# icetube.net
KiCad netlist of a schematic drawn in EAGLE
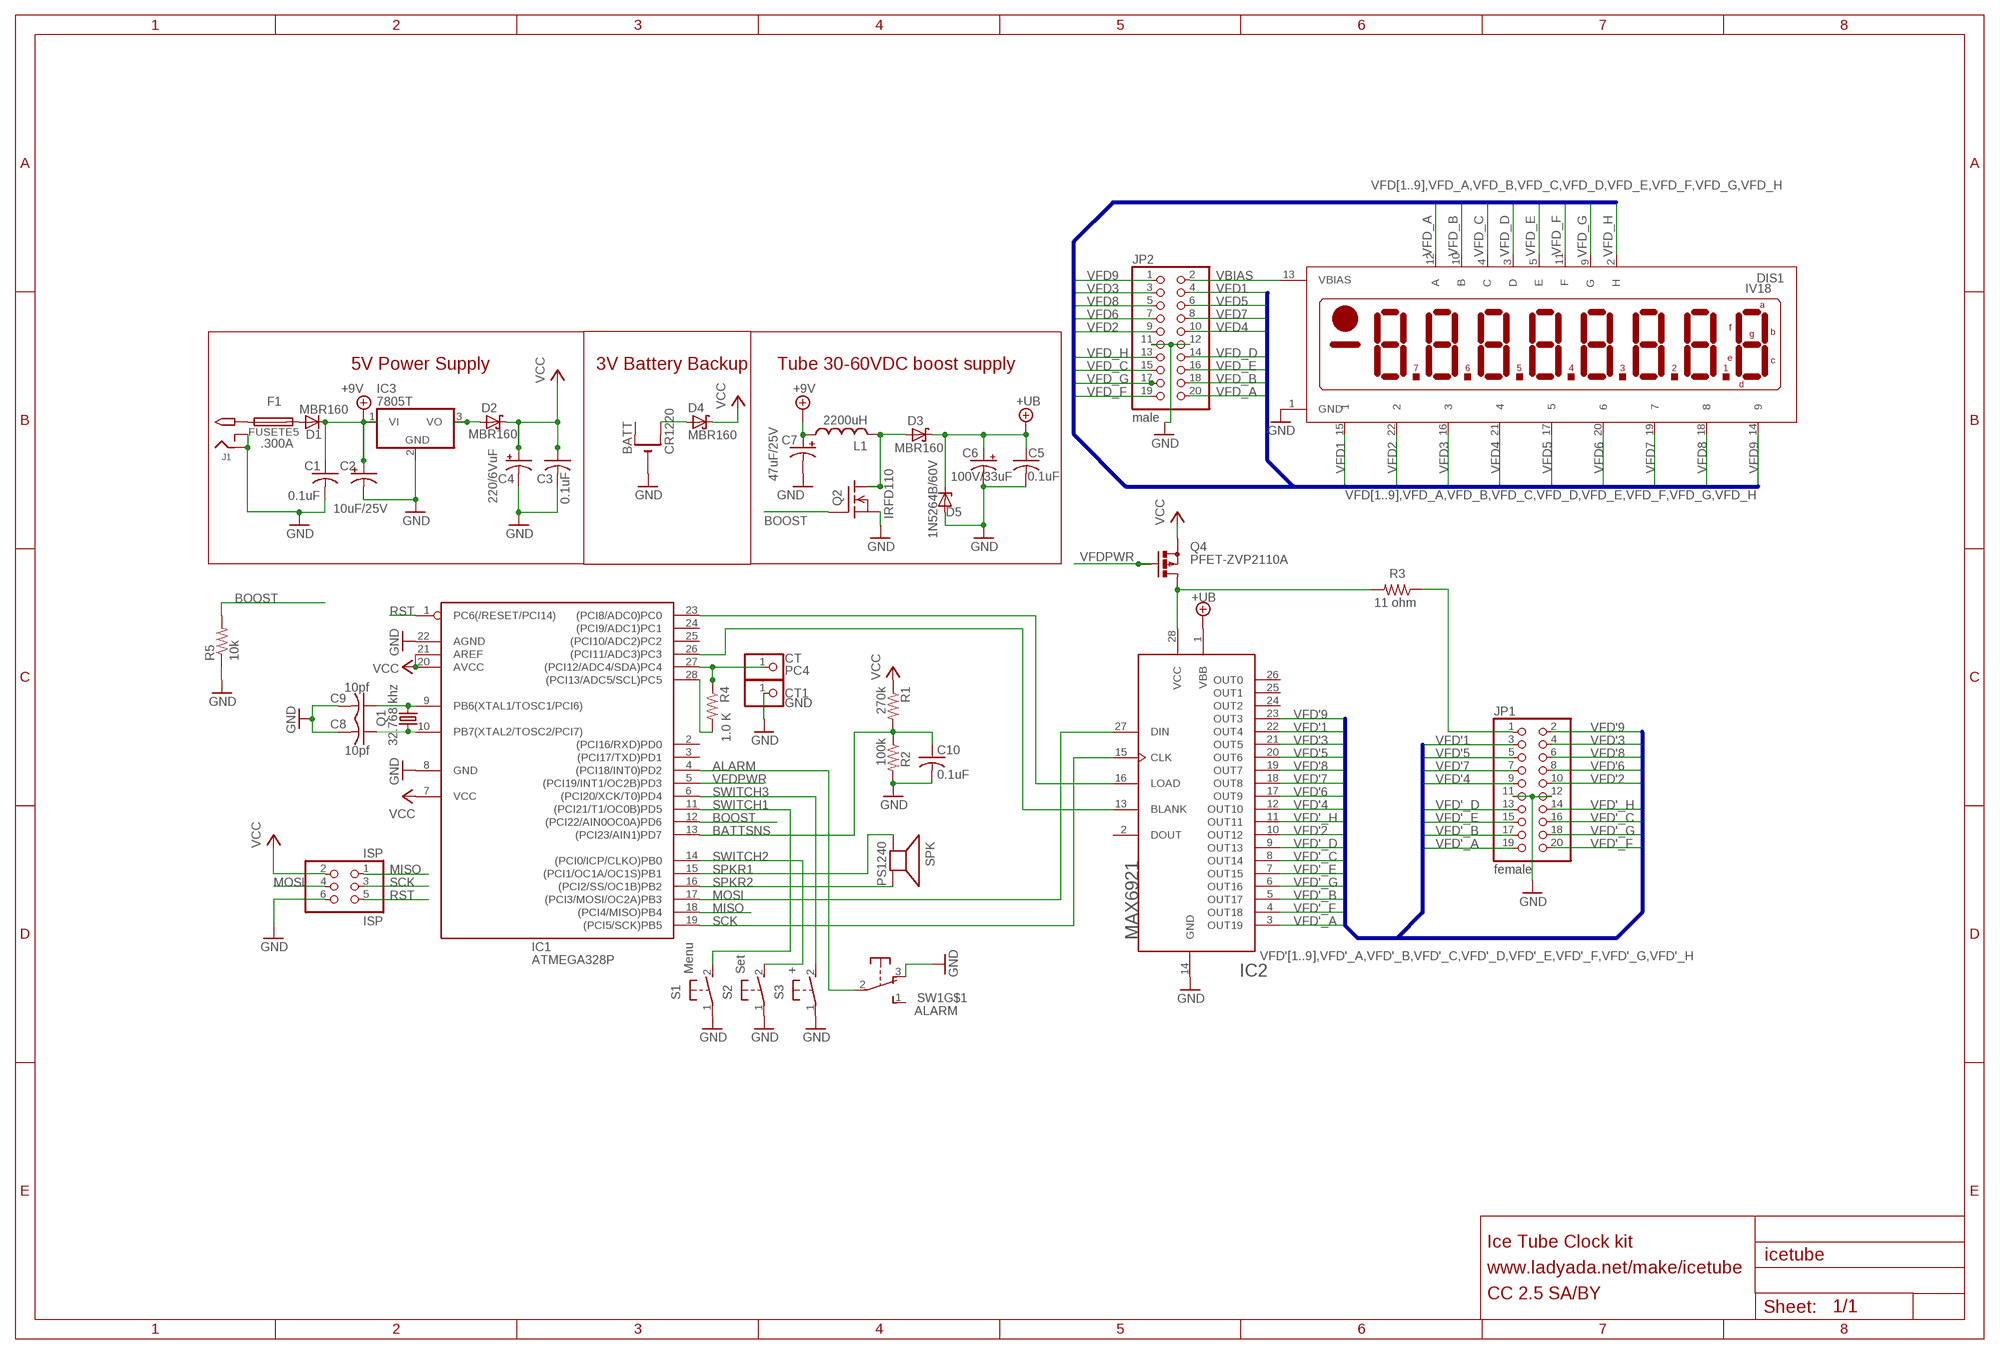
[diagram p0: schematic, sheet 1]

(export (version "E")
  (design (tool "Eeschema 10.0.6"))
  (components
    (comp (ref "BATT")
      (value "CR1220")
      (footprint "eagle-import:CR1220-THM")
      (libsource (lib "eagle-import") (part "CR1220THM"))
    )
    (comp (ref "C1")
      (value "0.1uF")
      (footprint "eagle-import:C025-025X050")
      (libsource (lib "eagle-import") (part "C-US025-025X050"))
    )
    (comp (ref "C2")
      (value "10uF/25V")
      (footprint "eagle-import:E2,5-6")
      (libsource (lib "eagle-import") (part "CPOL-USE2.5-6"))
    )
    (comp (ref "C3")
      (value "0.1uF")
      (footprint "eagle-import:C025-025X050")
      (libsource (lib "eagle-import") (part "C-US025-025X050"))
    )
    (comp (ref "C4")
      (value "220/6VuF")
      (footprint "eagle-import:E2,5-6")
      (libsource (lib "eagle-import") (part "CPOL-USE2.5-6"))
    )
    (comp (ref "C5")
      (value "0.1uF")
      (footprint "eagle-import:C025-024X044")
      (libsource (lib "eagle-import") (part "rcl-ez_C-US025-024X044"))
    )
    (comp (ref "C6")
      (value "100V/33uF")
      (footprint "eagle-import:E3,5-8")
      (libsource (lib "eagle-import") (part "rcl-ez_CPOL-USE3.5-8"))
    )
    (comp (ref "C7")
      (value "47uF/25V")
      (footprint "eagle-import:E2,5-6")
      (libsource (lib "eagle-import") (part "CPOL-USE2.5-6"))
    )
    (comp (ref "C8")
      (value "10pf")
      (footprint "eagle-import:C025-025X050")
      (libsource (lib "eagle-import") (part "C-US025-025X050"))
    )
    (comp (ref "C9")
      (value "10pf")
      (footprint "eagle-import:C025-025X050")
      (libsource (lib "eagle-import") (part "C-US025-025X050"))
    )
    (comp (ref "C10")
      (value "0.1uF")
      (footprint "eagle-import:C025-024X044")
      (libsource (lib "eagle-import") (part "rcl-ez_C-US025-024X044"))
    )
    (comp (ref "CT")
      (value "PC4")
      (footprint "eagle-import:1X01")
      (libsource (lib "eagle-import") (part "PINHD-1X1"))
    )
    (comp (ref "CT1")
      (value "GND")
      (footprint "eagle-import:1X01")
      (libsource (lib "eagle-import") (part "PINHD-1X1"))
    )
    (comp (ref "D1")
      (value "MBR160")
      (footprint "eagle-import:DO41-10")
      (libsource (lib "eagle-import") (part "1N4004"))
    )
    (comp (ref "D2")
      (value "MBR160")
      (footprint "eagle-import:DO41-10")
      (libsource (lib "eagle-import") (part "SCHOTTKY-DIODEDO41"))
    )
    (comp (ref "D3")
      (value "MBR160")
      (footprint "eagle-import:DO41-10")
      (libsource (lib "eagle-import") (part "SCHOTTKY-DIODEDO41"))
    )
    (comp (ref "D4")
      (value "MBR160")
      (footprint "eagle-import:DO41-10")
      (libsource (lib "eagle-import") (part "SCHOTTKY-DIODEDO41"))
    )
    (comp (ref "D5")
      (value "1N5264B/60V")
      (footprint "eagle-import:DO41Z10")
      (libsource (lib "eagle-import") (part "ZENER-DIODEDO41Z10"))
    )
    (comp (ref "DIS1")
      (value "IV18")
      (footprint "eagle-import:IV18")
      (libsource (lib "eagle-import") (part "IV18"))
    )
    (comp (ref "F1")
      (value "FUSETE5")
      (footprint "eagle-import:TE5")
      (fields (field (name "MF") ".300A"))
      (libsource (lib "eagle-import") (part "FUSETE5"))
    )
    (comp (ref "IC1")
      (value "ATMEGA328P")
      (footprint "eagle-import:DIL28_3")
      (libsource (lib "eagle-import") (part "ATMEGA168PROUND"))
    )
    (comp (ref "IC2")
      (value "MAX6921")
      (footprint "eagle-import:PLCC-S28")
      (libsource (lib "eagle-import") (part "MAX6921"))
    )
    (comp (ref "IC3")
      (value "7805T")
      (footprint "eagle-import:TO220H")
      (libsource (lib "eagle-import") (part "78T05"))
    )
    (comp (ref "ISP")
      (value "ISP")
      (footprint "eagle-import:2X03")
      (libsource (lib "eagle-import") (part "PINHD-2X3"))
    )
    (comp (ref "J1")
      (value "2.1MMJACKTHM")
      (footprint "eagle-import:PJ-102A")
      (libsource (lib "eagle-import") (part "2.1MMJACKTHM"))
    )
    (comp (ref "JP1")
      (value "female")
      (footprint "eagle-import:2X10")
      (libsource (lib "eagle-import") (part "PINHD-2X10"))
    )
    (comp (ref "JP2")
      (value "male")
      (footprint "eagle-import:2X10")
      (libsource (lib "eagle-import") (part "PINHD-2X10"))
    )
    (comp (ref "L1")
      (value "2200uH")
      (footprint "eagle-import:6000")
      (libsource (lib "eagle-import") (part "L"))
    )
    (comp (ref "Q1")
      (value "32.768 khz")
      (footprint "eagle-import:TC26V")
      (libsource (lib "eagle-import") (part "CRYTALTC26V"))
    )
    (comp (ref "Q2")
      (value "IRFD110")
      (footprint "eagle-import:DIL04")
      (libsource (lib "eagle-import") (part "IRFD110"))
    )
    (comp (ref "Q4")
      (value "PFET-ZVP2110A")
      (footprint "eagle-import:TO92-OVAL")
      (libsource (lib "eagle-import") (part "PFETZVP3306"))
    )
    (comp (ref "R1")
      (value "270k")
      (footprint "eagle-import:0207_10")
      (libsource (lib "eagle-import") (part "R-US_0207/10"))
    )
    (comp (ref "R2")
      (value "100k")
      (footprint "eagle-import:0207_10")
      (libsource (lib "eagle-import") (part "R-US_0207/10"))
    )
    (comp (ref "R3")
      (value "11 ohm")
      (footprint "eagle-import:0207_10")
      (libsource (lib "eagle-import") (part "R-US_0207/10"))
    )
    (comp (ref "R4")
      (value "1.0 K")
      (footprint "eagle-import:0207_5V")
      (libsource (lib "eagle-import") (part "R-US_0207/5V"))
    )
    (comp (ref "R5")
      (value "10k")
      (footprint "eagle-import:0207_5V")
      (libsource (lib "eagle-import") (part "R-US_0207/5V"))
    )
    (comp (ref "S1")
      (value "Menu")
      (footprint "eagle-import:B3F-31XX")
      (fields (field (name "MPN") "B3F-3100"))
      (libsource (lib "eagle-import") (part "31-XX"))
    )
    (comp (ref "S2")
      (value "Set")
      (footprint "eagle-import:B3F-31XX")
      (fields (field (name "MPN") "B3F-3100"))
      (libsource (lib "eagle-import") (part "31-XX"))
    )
    (comp (ref "S3")
      (value "+")
      (footprint "eagle-import:B3F-31XX")
      (fields (field (name "MPN") "B3F-3100"))
      (libsource (lib "eagle-import") (part "31-XX"))
    )
    (comp (ref "SPK")
      (value "PS1240")
      (footprint "eagle-import:PS12")
      (libsource (lib "eagle-import") (part "SPEAKER/PS12"))
    )
    (comp (ref "SW1")
      (value "ALARM")
      (footprint "eagle-import:OS102011MA1Q")
      (libsource (lib "eagle-import") (part "OS102011MA1Q"))
    )
  )
  (nets
    (net (code "1") (name "+9V") (class "Default")
      (node (ref "C1") (pin "1") (pinfunction "1_1") (pintype "passive"))
      (node (ref "C2") (pin "+") (pinfunction "+_+") (pintype "passive"))
      (node (ref "C7") (pin "+") (pinfunction "+_+") (pintype "passive"))
      (node (ref "D1") (pin "C") (pinfunction "C_C") (pintype "passive"))
      (node (ref "IC3") (pin "1") (pinfunction "VI_1") (pintype "input"))
      (node (ref "L1") (pin "1") (pinfunction "1_1") (pintype "passive"))
    )
    (net (code "2") (name "+UB") (class "Default")
      (node (ref "C5") (pin "1") (pinfunction "1_1") (pintype "passive"))
      (node (ref "C6") (pin "+") (pinfunction "+_+") (pintype "passive"))
      (node (ref "D3") (pin "C") (pinfunction "C_C") (pintype "passive"))
      (node (ref "D5") (pin "C") (pinfunction "C_C") (pintype "passive"))
      (node (ref "IC2") (pin "1") (pinfunction "VBB_1") (pintype "power_in"))
    )
    (net (code "3") (name "/ALARM") (class "Default")
      (node (ref "IC1") (pin "4") (pinfunction "(PCI18/INT0)PD2_4") (pintype "bidirectional"))
      (node (ref "SW1") (pin "2") (pinfunction "P_2") (pintype "passive"))
    )
    (net (code "4") (name "/BATTSNS") (class "Default")
      (node (ref "C10") (pin "1") (pinfunction "1_1") (pintype "passive"))
      (node (ref "IC1") (pin "13") (pinfunction "(PCI23/AIN1)PD7_13") (pintype "bidirectional"))
      (node (ref "R1") (pin "2") (pinfunction "2_2") (pintype "passive"))
      (node (ref "R2") (pin "1") (pinfunction "1_1") (pintype "passive"))
    )
    (net (code "5") (name "/BOOST") (class "Default")
      (node (ref "IC1") (pin "12") (pinfunction "(PCI22/AIN0OC0A)PD6_12") (pintype "bidirectional"))
      (node (ref "Q2") (pin "3") (pinfunction "G_3") (pintype "passive"))
      (node (ref "R5") (pin "2") (pinfunction "2_2") (pintype "passive"))
    )
    (net (code "6") (name "/MISO") (class "Default")
      (node (ref "IC1") (pin "18") (pinfunction "(PCI4/MISO)PB4_18") (pintype "bidirectional"))
      (node (ref "ISP") (pin "1") (pinfunction "1_1") (pintype "passive"))
    )
    (net (code "7") (name "/MOSI") (class "Default")
      (node (ref "IC1") (pin "17") (pinfunction "(PCI3/MOSI/OC2A)PB3_17") (pintype "bidirectional"))
      (node (ref "IC2") (pin "27") (pinfunction "DIN_27") (pintype "input"))
      (node (ref "ISP") (pin "4") (pinfunction "4_4") (pintype "passive"))
    )
    (net (code "8") (name "/RST") (class "Default")
      (node (ref "IC1") (pin "1") (pinfunction "PC6(/RESET/PCI14)_1") (pintype "bidirectional"))
      (node (ref "ISP") (pin "5") (pinfunction "5_5") (pintype "passive"))
    )
    (net (code "9") (name "/SCK") (class "Default")
      (node (ref "IC1") (pin "19") (pinfunction "(PCI5/SCK)PB5_19") (pintype "bidirectional"))
      (node (ref "IC2") (pin "15") (pinfunction "CLK_15") (pintype "input"))
      (node (ref "ISP") (pin "3") (pinfunction "3_3") (pintype "passive"))
    )
    (net (code "10") (name "/SPKR1") (class "Default")
      (node (ref "IC1") (pin "15") (pinfunction "(PCI1/OC1A/OC1S)PB1_15") (pintype "bidirectional"))
      (node (ref "SPK") (pin "P$1") (pinfunction "+_P$1") (pintype "passive"))
    )
    (net (code "11") (name "/SPKR2") (class "Default")
      (node (ref "IC1") (pin "16") (pinfunction "(PCI2/SS/OC1B)PB2_16") (pintype "bidirectional"))
      (node (ref "SPK") (pin "P$2") (pinfunction "-_P$2") (pintype "passive"))
    )
    (net (code "12") (name "/SWITCH1") (class "Default")
      (node (ref "IC1") (pin "11") (pinfunction "(PCI21/T1/OC0B)PD5_11") (pintype "bidirectional"))
      (node (ref "S1") (pin "2") (pinfunction "S_2") (pintype "passive"))
    )
    (net (code "13") (name "/SWITCH2") (class "Default")
      (node (ref "IC1") (pin "14") (pinfunction "(PCI0/ICP/CLKO)PB0_14") (pintype "bidirectional"))
      (node (ref "S2") (pin "2") (pinfunction "S_2") (pintype "passive"))
    )
    (net (code "14") (name "/SWITCH3") (class "Default")
      (node (ref "IC1") (pin "6") (pinfunction "(PCI20/XCK/T0)PD4_6") (pintype "bidirectional"))
      (node (ref "S3") (pin "2") (pinfunction "S_2") (pintype "passive"))
    )
    (net (code "15") (name "/VBIAS") (class "Default")
      (node (ref "DIS1") (pin "13") (pinfunction "VBIAS_13") (pintype "power_in"))
      (node (ref "JP2") (pin "2") (pinfunction "2_2") (pintype "passive"))
    )
    (net (code "16") (name "/VFD'1") (class "Default")
      (node (ref "IC2") (pin "22") (pinfunction "OUT4_22") (pintype "output"))
      (node (ref "JP1") (pin "3") (pinfunction "3_3") (pintype "passive"))
    )
    (net (code "17") (name "/VFD'2") (class "Default")
      (node (ref "IC2") (pin "10") (pinfunction "OUT12_10") (pintype "output"))
      (node (ref "JP1") (pin "10") (pinfunction "10_10") (pintype "passive"))
    )
    (net (code "18") (name "/VFD'3") (class "Default")
      (node (ref "IC2") (pin "21") (pinfunction "OUT5_21") (pintype "output"))
      (node (ref "JP1") (pin "4") (pinfunction "4_4") (pintype "passive"))
    )
    (net (code "19") (name "/VFD'4") (class "Default")
      (node (ref "IC2") (pin "12") (pinfunction "OUT10_12") (pintype "output"))
      (node (ref "JP1") (pin "9") (pinfunction "9_9") (pintype "passive"))
    )
    (net (code "20") (name "/VFD'5") (class "Default")
      (node (ref "IC2") (pin "20") (pinfunction "OUT6_20") (pintype "output"))
      (node (ref "JP1") (pin "5") (pinfunction "5_5") (pintype "passive"))
    )
    (net (code "21") (name "/VFD'6") (class "Default")
      (node (ref "IC2") (pin "17") (pinfunction "OUT9_17") (pintype "output"))
      (node (ref "JP1") (pin "8") (pinfunction "8_8") (pintype "passive"))
    )
    (net (code "22") (name "/VFD'7") (class "Default")
      (node (ref "IC2") (pin "18") (pinfunction "OUT8_18") (pintype "output"))
      (node (ref "JP1") (pin "7") (pinfunction "7_7") (pintype "passive"))
    )
    (net (code "23") (name "/VFD'8") (class "Default")
      (node (ref "IC2") (pin "19") (pinfunction "OUT7_19") (pintype "output"))
      (node (ref "JP1") (pin "6") (pinfunction "6_6") (pintype "passive"))
    )
    (net (code "24") (name "/VFD'9") (class "Default")
      (node (ref "IC2") (pin "23") (pinfunction "OUT3_23") (pintype "output"))
      (node (ref "JP1") (pin "2") (pinfunction "2_2") (pintype "passive"))
    )
    (net (code "25") (name "/VFD'_A") (class "Default")
      (node (ref "IC2") (pin "3") (pinfunction "OUT19_3") (pintype "output"))
      (node (ref "JP1") (pin "19") (pinfunction "19_19") (pintype "passive"))
    )
    (net (code "26") (name "/VFD'_B") (class "Default")
      (node (ref "IC2") (pin "5") (pinfunction "OUT17_5") (pintype "output"))
      (node (ref "JP1") (pin "17") (pinfunction "17_17") (pintype "passive"))
    )
    (net (code "27") (name "/VFD'_C") (class "Default")
      (node (ref "IC2") (pin "8") (pinfunction "OUT14_8") (pintype "output"))
      (node (ref "JP1") (pin "16") (pinfunction "16_16") (pintype "passive"))
    )
    (net (code "28") (name "/VFD'_D") (class "Default")
      (node (ref "IC2") (pin "9") (pinfunction "OUT13_9") (pintype "output"))
      (node (ref "JP1") (pin "13") (pinfunction "13_13") (pintype "passive"))
    )
    (net (code "29") (name "/VFD'_E") (class "Default")
      (node (ref "IC2") (pin "7") (pinfunction "OUT15_7") (pintype "output"))
      (node (ref "JP1") (pin "15") (pinfunction "15_15") (pintype "passive"))
    )
    (net (code "30") (name "/VFD'_F") (class "Default")
      (node (ref "IC2") (pin "4") (pinfunction "OUT18_4") (pintype "output"))
      (node (ref "JP1") (pin "20") (pinfunction "20_20") (pintype "passive"))
    )
    (net (code "31") (name "/VFD'_G") (class "Default")
      (node (ref "IC2") (pin "6") (pinfunction "OUT16_6") (pintype "output"))
      (node (ref "JP1") (pin "18") (pinfunction "18_18") (pintype "passive"))
    )
    (net (code "32") (name "/VFD'_H") (class "Default")
      (node (ref "IC2") (pin "11") (pinfunction "OUT11_11") (pintype "output"))
      (node (ref "JP1") (pin "14") (pinfunction "14_14") (pintype "passive"))
    )
    (net (code "33") (name "/VFD1") (class "Default")
      (node (ref "DIS1") (pin "15") (pinfunction "1_15") (pintype "passive"))
      (node (ref "JP2") (pin "4") (pinfunction "4_4") (pintype "passive"))
    )
    (net (code "34") (name "/VFD2") (class "Default")
      (node (ref "DIS1") (pin "22") (pinfunction "2_22") (pintype "passive"))
      (node (ref "JP2") (pin "9") (pinfunction "9_9") (pintype "passive"))
    )
    (net (code "35") (name "/VFD3") (class "Default")
      (node (ref "DIS1") (pin "16") (pinfunction "3_16") (pintype "passive"))
      (node (ref "JP2") (pin "3") (pinfunction "3_3") (pintype "passive"))
    )
    (net (code "36") (name "/VFD4") (class "Default")
      (node (ref "DIS1") (pin "21") (pinfunction "4_21") (pintype "passive"))
      (node (ref "JP2") (pin "10") (pinfunction "10_10") (pintype "passive"))
    )
    (net (code "37") (name "/VFD5") (class "Default")
      (node (ref "DIS1") (pin "17") (pinfunction "5_17") (pintype "passive"))
      (node (ref "JP2") (pin "6") (pinfunction "6_6") (pintype "passive"))
    )
    (net (code "38") (name "/VFD6") (class "Default")
      (node (ref "DIS1") (pin "20") (pinfunction "6_20") (pintype "passive"))
      (node (ref "JP2") (pin "7") (pinfunction "7_7") (pintype "passive"))
    )
    (net (code "39") (name "/VFD7") (class "Default")
      (node (ref "DIS1") (pin "19") (pinfunction "7_19") (pintype "passive"))
      (node (ref "JP2") (pin "8") (pinfunction "8_8") (pintype "passive"))
    )
    (net (code "40") (name "/VFD8") (class "Default")
      (node (ref "DIS1") (pin "18") (pinfunction "8_18") (pintype "passive"))
      (node (ref "JP2") (pin "5") (pinfunction "5_5") (pintype "passive"))
    )
    (net (code "41") (name "/VFD9") (class "Default")
      (node (ref "DIS1") (pin "14") (pinfunction "9_14") (pintype "passive"))
      (node (ref "JP2") (pin "1") (pinfunction "1_1") (pintype "passive"))
    )
    (net (code "42") (name "/VFDPWR") (class "Default")
      (node (ref "IC1") (pin "5") (pinfunction "(PCI19/INT1/OC2B)PD3_5") (pintype "bidirectional"))
      (node (ref "Q4") (pin "2") (pinfunction "G_2") (pintype "passive"))
    )
    (net (code "43") (name "/VFD_A") (class "Default")
      (node (ref "DIS1") (pin "12") (pinfunction "A_12") (pintype "passive"))
      (node (ref "JP2") (pin "20") (pinfunction "20_20") (pintype "passive"))
    )
    (net (code "44") (name "/VFD_B") (class "Default")
      (node (ref "DIS1") (pin "10") (pinfunction "B_10") (pintype "passive"))
      (node (ref "JP2") (pin "18") (pinfunction "18_18") (pintype "passive"))
    )
    (net (code "45") (name "/VFD_C") (class "Default")
      (node (ref "DIS1") (pin "4") (pinfunction "C_4") (pintype "passive"))
      (node (ref "JP2") (pin "15") (pinfunction "15_15") (pintype "passive"))
    )
    (net (code "46") (name "/VFD_D") (class "Default")
      (node (ref "DIS1") (pin "3") (pinfunction "D_3") (pintype "passive"))
      (node (ref "JP2") (pin "14") (pinfunction "14_14") (pintype "passive"))
    )
    (net (code "47") (name "/VFD_E") (class "Default")
      (node (ref "DIS1") (pin "5") (pinfunction "E_5") (pintype "passive"))
      (node (ref "JP2") (pin "16") (pinfunction "16_16") (pintype "passive"))
    )
    (net (code "48") (name "/VFD_F") (class "Default")
      (node (ref "DIS1") (pin "11") (pinfunction "F_11") (pintype "passive"))
      (node (ref "JP2") (pin "19") (pinfunction "19_19") (pintype "passive"))
    )
    (net (code "49") (name "/VFD_G") (class "Default")
      (node (ref "DIS1") (pin "9") (pinfunction "G_9") (pintype "passive"))
      (node (ref "JP2") (pin "17") (pinfunction "17_17") (pintype "passive"))
    )
    (net (code "50") (name "/VFD_H") (class "Default")
      (node (ref "DIS1") (pin "2") (pinfunction "H_2") (pintype "passive"))
      (node (ref "JP2") (pin "13") (pinfunction "13_13") (pintype "passive"))
    )
    (net (code "53") (name "GND") (class "Default")
      (node (ref "BATT") (pin "-") (pinfunction "-_-") (pintype "passive"))
      (node (ref "C1") (pin "2") (pinfunction "2_2") (pintype "passive"))
      (node (ref "C10") (pin "2") (pinfunction "2_2") (pintype "passive"))
      (node (ref "C2") (pin "-") (pinfunction "-_-") (pintype "passive"))
      (node (ref "C3") (pin "2") (pinfunction "2_2") (pintype "passive"))
      (node (ref "C4") (pin "-") (pinfunction "-_-") (pintype "passive"))
      (node (ref "C5") (pin "2") (pinfunction "2_2") (pintype "passive"))
      (node (ref "C6") (pin "-") (pinfunction "-_-") (pintype "passive"))
      (node (ref "C7") (pin "-") (pinfunction "-_-") (pintype "passive"))
      (node (ref "C8") (pin "2") (pinfunction "2_2") (pintype "passive"))
      (node (ref "C9") (pin "2") (pinfunction "2_2") (pintype "passive"))
      (node (ref "CT1") (pin "1") (pinfunction "1_1") (pintype "passive"))
      (node (ref "D5") (pin "A") (pinfunction "A_A") (pintype "passive"))
      (node (ref "DIS1") (pin "1") (pinfunction "GND_1") (pintype "power_in"))
      (node (ref "IC1") (pin "22") (pinfunction "AGND_22") (pintype "bidirectional"))
      (node (ref "IC1") (pin "8") (pinfunction "GND_8") (pintype "bidirectional"))
      (node (ref "IC2") (pin "14") (pinfunction "GND_14") (pintype "power_in"))
      (node (ref "IC3") (pin "2") (pinfunction "GND_2") (pintype "passive"))
      (node (ref "ISP") (pin "6") (pinfunction "6_6") (pintype "passive"))
      (node (ref "J1") (pin "RING") (pinfunction "RING_RING") (pintype "bidirectional"))
      (node (ref "J1") (pin "RING_SW") (pinfunction "RING_SW_RING_SW") (pintype "bidirectional"))
      (node (ref "JP1") (pin "11") (pinfunction "11_11") (pintype "passive"))
      (node (ref "JP1") (pin "12") (pinfunction "12_12") (pintype "passive"))
      (node (ref "JP2") (pin "11") (pinfunction "11_11") (pintype "passive"))
      (node (ref "JP2") (pin "12") (pinfunction "12_12") (pintype "passive"))
      (node (ref "Q2") (pin "4") (pinfunction "S_4") (pintype "passive"))
      (node (ref "R2") (pin "2") (pinfunction "2_2") (pintype "passive"))
      (node (ref "R5") (pin "1") (pinfunction "1_1") (pintype "passive"))
      (node (ref "S1") (pin "1") (pinfunction "P_1") (pintype "passive"))
      (node (ref "S2") (pin "1") (pinfunction "P_1") (pintype "passive"))
      (node (ref "S3") (pin "1") (pinfunction "P_1") (pintype "passive"))
      (node (ref "SW1") (pin "3") (pinfunction "O_3") (pintype "passive"))
    )
    (net (code "54") (name "Net-(BATT-+1)") (class "Default")
      (node (ref "BATT") (pin "+2") (pinfunction "+1_+2") (pintype "passive"))
      (node (ref "D4") (pin "A") (pinfunction "A_A") (pintype "passive"))
    )
    (net (code "55") (name "Net-(D1-PadA)") (class "Default")
      (node (ref "D1") (pin "A") (pinfunction "A_A") (pintype "passive"))
      (node (ref "F1") (pin "2") (pinfunction "2_2") (pintype "passive"))
    )
    (net (code "56") (name "Net-(F1-Pad1)") (class "Default")
      (node (ref "F1") (pin "1") (pinfunction "1_1") (pintype "passive"))
      (node (ref "J1") (pin "TIP") (pinfunction "TIP_TIP") (pintype "bidirectional"))
    )
    (net (code "57") (name "Net-(IC1-(PCI8{slash}ADC0)PC0)") (class "Default")
      (node (ref "IC1") (pin "23") (pinfunction "(PCI8/ADC0)PC0_23") (pintype "bidirectional"))
      (node (ref "IC2") (pin "16") (pinfunction "LOAD_16") (pintype "input"))
    )
    (net (code "58") (name "Net-(IC1-(PCI11{slash}ADC3)PC3)") (class "Default")
      (node (ref "IC1") (pin "26") (pinfunction "(PCI11/ADC3)PC3_26") (pintype "bidirectional"))
      (node (ref "IC2") (pin "13") (pinfunction "BLANK_13") (pintype "input"))
    )
    (net (code "59") (name "Net-(IC1-(PCI12{slash}ADC4{slash}SDA)PC4)") (class "Default")
      (node (ref "CT") (pin "1") (pinfunction "1_1") (pintype "passive"))
      (node (ref "IC1") (pin "27") (pinfunction "(PCI12/ADC4/SDA)PC4_27") (pintype "bidirectional"))
      (node (ref "R4") (pin "1") (pinfunction "1_1") (pintype "passive"))
    )
    (net (code "60") (name "Net-(IC1-(PCI13{slash}ADC5{slash}SCL)PC5)") (class "Default")
      (node (ref "IC1") (pin "28") (pinfunction "(PCI13/ADC5/SCL)PC5_28") (pintype "bidirectional"))
      (node (ref "R4") (pin "2") (pinfunction "2_2") (pintype "passive"))
    )
    (net (code "61") (name "Net-(IC1-PB6(XTAL1{slash}TOSC1{slash}PCI6))") (class "Default")
      (node (ref "C9") (pin "1") (pinfunction "1_1") (pintype "passive"))
      (node (ref "IC1") (pin "9") (pinfunction "PB6(XTAL1/TOSC1/PCI6)_9") (pintype "bidirectional"))
      (node (ref "Q1") (pin "2") (pinfunction "2_2") (pintype "passive"))
    )
    (net (code "62") (name "Net-(IC1-PB7(XTAL2{slash}TOSC2{slash}PCI7))") (class "Default")
      (node (ref "C8") (pin "1") (pinfunction "1_1") (pintype "passive"))
      (node (ref "IC1") (pin "10") (pinfunction "PB7(XTAL2/TOSC2/PCI7)_10") (pintype "bidirectional"))
      (node (ref "Q1") (pin "1") (pinfunction "1_1") (pintype "passive"))
    )
    (net (code "63") (name "Net-(IC2-VCC)") (class "Default")
      (node (ref "IC2") (pin "28") (pinfunction "VCC_28") (pintype "power_in"))
      (node (ref "Q4") (pin "3") (pinfunction "D_3") (pintype "passive"))
      (node (ref "R3") (pin "2") (pinfunction "2_2") (pintype "passive"))
    )
    (net (code "64") (name "Net-(IC3-VO)") (class "Default")
      (node (ref "D2") (pin "A") (pinfunction "A_A") (pintype "passive"))
      (node (ref "IC3") (pin "3") (pinfunction "VO_3") (pintype "passive"))
    )
    (net (code "65") (name "Net-(JP1-Pad1)") (class "Default")
      (node (ref "JP1") (pin "1") (pinfunction "1_1") (pintype "passive"))
      (node (ref "R3") (pin "1") (pinfunction "1_1") (pintype "passive"))
    )
    (net (code "66") (name "Net-(Q2-D)") (class "Default")
      (node (ref "D3") (pin "A") (pinfunction "A_A") (pintype "passive"))
      (node (ref "L1") (pin "2") (pinfunction "2_2") (pintype "passive"))
      (node (ref "Q2") (pin "1") (pinfunction "D_1") (pintype "passive"))
      (node (ref "Q2") (pin "2") (pinfunction "D1_2") (pintype "passive"))
    )
    (net (code "67") (name "VCC") (class "Default")
      (node (ref "C3") (pin "1") (pinfunction "1_1") (pintype "passive"))
      (node (ref "C4") (pin "+") (pinfunction "+_+") (pintype "passive"))
      (node (ref "D2") (pin "C") (pinfunction "C_C") (pintype "passive"))
      (node (ref "D4") (pin "C") (pinfunction "C_C") (pintype "passive"))
      (node (ref "IC1") (pin "20") (pinfunction "AVCC_20") (pintype "bidirectional"))
      (node (ref "IC1") (pin "21") (pinfunction "AREF_21") (pintype "bidirectional"))
      (node (ref "IC1") (pin "7") (pinfunction "VCC_7") (pintype "bidirectional"))
      (node (ref "ISP") (pin "2") (pinfunction "2_2") (pintype "passive"))
      (node (ref "Q4") (pin "1") (pinfunction "S_1") (pintype "passive"))
      (node (ref "R1") (pin "1") (pinfunction "1_1") (pintype "passive"))
    )
    (net (code "68") (name "unconnected-(BATT-+-Pad+1)") (class "Default")
      (node (ref "BATT") (pin "+1") (pinfunction "+_+1") (pintype "passive"))
    )
    (net (code "69") (name "unconnected-(IC1-(PCI9{slash}ADC1)PC1-Pad24)") (class "Default")
      (node (ref "IC1") (pin "24") (pinfunction "(PCI9/ADC1)PC1_24") (pintype "bidirectional"))
    )
    (net (code "70") (name "unconnected-(IC1-(PCI10{slash}ADC2)PC2-Pad25)") (class "Default")
      (node (ref "IC1") (pin "25") (pinfunction "(PCI10/ADC2)PC2_25") (pintype "bidirectional"))
    )
    (net (code "71") (name "unconnected-(IC1-(PCI16{slash}RXD)PD0-Pad2)") (class "Default")
      (node (ref "IC1") (pin "2") (pinfunction "(PCI16/RXD)PD0_2") (pintype "bidirectional"))
    )
    (net (code "72") (name "unconnected-(IC1-(PCI17{slash}TXD)PD1-Pad3)") (class "Default")
      (node (ref "IC1") (pin "3") (pinfunction "(PCI17/TXD)PD1_3") (pintype "bidirectional"))
    )
    (net (code "73") (name "unconnected-(IC2-DOUT-Pad2)") (class "Default")
      (node (ref "IC2") (pin "2") (pinfunction "DOUT_2") (pintype "output"))
    )
    (net (code "74") (name "unconnected-(IC2-OUT0-Pad26)") (class "Default")
      (node (ref "IC2") (pin "26") (pinfunction "OUT0_26") (pintype "output"))
    )
    (net (code "75") (name "unconnected-(IC2-OUT1-Pad25)") (class "Default")
      (node (ref "IC2") (pin "25") (pinfunction "OUT1_25") (pintype "output"))
    )
    (net (code "76") (name "unconnected-(IC2-OUT2-Pad24)") (class "Default")
      (node (ref "IC2") (pin "24") (pinfunction "OUT2_24") (pintype "output"))
    )
    (net (code "77") (name "unconnected-(SW1A-S-Pad1)") (class "Default")
      (node (ref "SW1") (pin "1") (pinfunction "S_1") (pintype "passive"))
    )
  )
)
